# design.net
KiCad netlist of a schematic drawn in Altium Designer
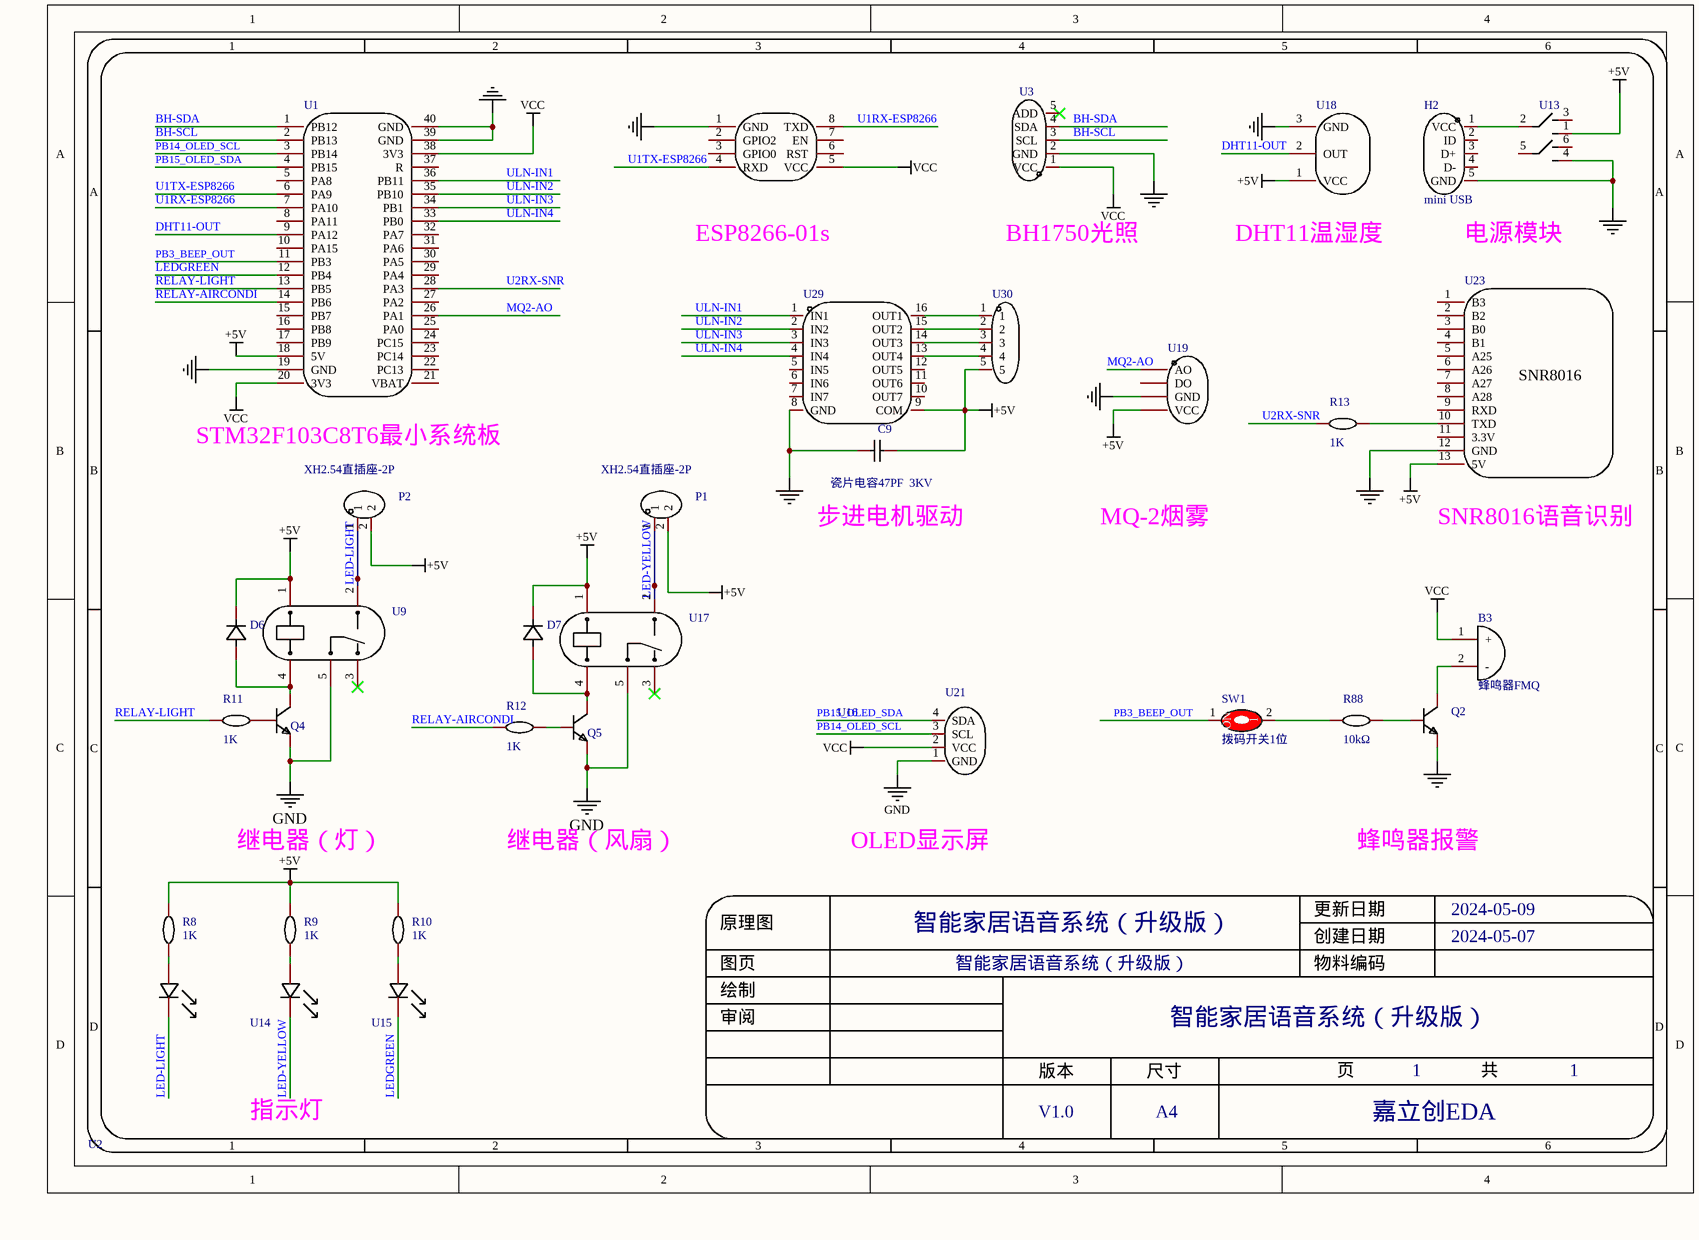
[diagram p0: 原理图.schdoc]

(export (version "E")
  (design (tool "Eeschema 10.0.6"))
  (components
    (comp (ref "B3")
      (value "蜂鸣器FMQ")
      (footprint "蜂鸣器")
      (fields (field (name "NAME") "蜂鸣器FMQ"))
      (libsource (lib "altium-import") (part "root_0_蜂鸣器FMQ_"))
    )
    (comp (ref "C9")
      (value "瓷片电容47PF  3KV")
      (footprint "CAP-TH_L5.0-W4.0-P5.00-D1.0")
      (fields (field (name "NAME") "瓷片电容47PF  3KV"))
      (libsource (lib "altium-import") (part "root_0_瓷片电容47PF  3KV_"))
    )
    (comp (ref "D6")
      (value "D_1N4007A")
      (footprint "DO_1N4007")
      (libsource (lib "altium-import") (part "root_1_D_1N4007A_"))
    )
    (comp (ref "D7")
      (value "D_1N4007A")
      (footprint "DO_1N4007")
      (libsource (lib "altium-import") (part "root_1_D_1N4007A_"))
    )
    (comp (ref "H2")
      (value "mini USB")
      (footprint "MINI-USB-POWER")
      (fields (field (name "NAME") "mini USB"))
      (libsource (lib "altium-import") (part "root_0_mini USB_"))
    )
    (comp (ref "P1")
      (value "XH2.54直插座-2P")
      (footprint "CONN-TH_XH2.54-2P")
      (fields (field (name "NAME") "XH2.54直插座-2P"))
      (libsource (lib "altium-import") (part "root_1_XH2.54直插座-2P_"))
    )
    (comp (ref "P2")
      (value "XH2.54直插座-2P")
      (footprint "CONN-TH_XH2.54-2P")
      (fields (field (name "NAME") "XH2.54直插座-2P"))
      (libsource (lib "altium-import") (part "root_1_XH2.54直插座-2P_"))
    )
    (comp (ref "Q2")
      (value "S8050_TO_NPN")
      (footprint "S8050_TO_92")
      (libsource (lib "altium-import") (part "root_0_S8050_TO_NPN_"))
    )
    (comp (ref "Q4")
      (value "S8050_TO_NPN")
      (footprint "S8050_TO_92")
      (libsource (lib "altium-import") (part "root_0_S8050_TO_NPN_"))
    )
    (comp (ref "Q5")
      (value "S8050_TO_NPN")
      (footprint "S8050_TO_92")
      (libsource (lib "altium-import") (part "root_0_S8050_TO_NPN_"))
    )
    (comp (ref "R8")
      (value "1K")
      (footprint "Res_1/4W")
      (fields (field (name "NAME") "1K"))
      (libsource (lib "altium-import") (part "root_1_Res_AXIAL-1/4W_"))
    )
    (comp (ref "R9")
      (value "1K")
      (footprint "Res_1/4W")
      (fields (field (name "NAME") "1K"))
      (libsource (lib "altium-import") (part "root_1_Res_AXIAL-1/4W_"))
    )
    (comp (ref "R10")
      (value "1K")
      (footprint "Res_1/4W")
      (fields (field (name "NAME") "1K"))
      (libsource (lib "altium-import") (part "root_1_Res_AXIAL-1/4W_"))
    )
    (comp (ref "R11")
      (value "1K")
      (footprint "Res_1/4W")
      (fields (field (name "NAME") "1K"))
      (libsource (lib "altium-import") (part "root_2_Res_AXIAL-1/4W_"))
    )
    (comp (ref "R12")
      (value "1K")
      (footprint "Res_1/4W")
      (fields (field (name "NAME") "1K"))
      (libsource (lib "altium-import") (part "root_2_Res_AXIAL-1/4W_"))
    )
    (comp (ref "R13")
      (value "1K")
      (footprint "Res_1/4W")
      (fields (field (name "NAME") "1K"))
      (libsource (lib "altium-import") (part "root_2_Res_AXIAL-1/4W_"))
    )
    (comp (ref "R88")
      (value "10kΩ")
      (footprint "Res_1/4W")
      (fields (field (name "NAME") "10kΩ"))
      (libsource (lib "altium-import") (part "root_0_Res_AXIAL-1/4W_"))
    )
    (comp (ref "SW1")
      (value "拨码开关1位")
      (footprint "SW-TH_DSWB01LHGET")
      (fields (field (name "NAME") "拨码开关1位"))
      (libsource (lib "altium-import") (part "root_1_拨码开关1位_"))
    )
    (comp (ref "U1")
      (value "STM32F103C8T6小蓝板")
      (footprint "STM32F103C8T6最小系统板(蓝)")
      (libsource (lib "altium-import") (part "root_0_STM32F103C8T6小蓝板_"))
    )
    (comp (ref "U2")
      (value "ESP8266-01S模块")
      (footprint "ESP8266-01S模块")
      (libsource (lib "altium-import") (part "root_0_ESP8266-01S模块_"))
    )
    (comp (ref "U3")
      (value "GY302光照传感器")
      (footprint "GY302光照传感器")
      (libsource (lib "altium-import") (part "root_0_GY302光照传感器_"))
    )
    (comp (ref "U9")
      (value "继电器5V")
      (footprint "继电器DC5V")
      (libsource (lib "altium-import") (part "root_3_继电器5V_"))
    )
    (comp (ref "U13")
      (value "按键开关7*7")
      (footprint "按键开关7*7")
      (libsource (lib "altium-import") (part "root_0_按键开关7*7_"))
    )
    (comp (ref "U14")
      (value "LED_5mm")
      (footprint "LED_5mm")
      (libsource (lib "altium-import") (part "root_3_LED_5mm_"))
    )
    (comp (ref "U15")
      (value "LED_5mm")
      (footprint "LED_5mm")
      (libsource (lib "altium-import") (part "root_3_LED_5mm_"))
    )
    (comp (ref "U16")
      (value "LED_5mm")
      (footprint "LED_5mm")
      (libsource (lib "altium-import") (part "root_3_LED_5mm_"))
    )
    (comp (ref "U17")
      (value "继电器5V")
      (footprint "继电器DC5V")
      (libsource (lib "altium-import") (part "root_3_继电器5V_"))
    )
    (comp (ref "U18")
      (value "DHT11温湿度传感器")
      (footprint "DHT11")
      (libsource (lib "altium-import") (part "root_0_DHT11温湿度传感器_"))
    )
    (comp (ref "U19")
      (value "MQ系列4针传感器")
      (footprint "MQ系列4针传感器")
      (libsource (lib "altium-import") (part "root_0_MQ系列4针传感器_"))
    )
    (comp (ref "U21")
      (value "OLED四针0.96寸")
      (footprint "OLED4针0.96寸")
      (libsource (lib "altium-import") (part "root_0_OLED四针0.96寸_"))
    )
    (comp (ref "U23")
      (value "SNR8016语音识别")
      (footprint "SNR8016")
      (libsource (lib "altium-import") (part "root_0_SNR8016语音识别_"))
    )
    (comp (ref "U29")
      (value "ULN2003A")
      (footprint "DIP-16_L20.0-W6.4-P2.54-LS7.6-BL")
      (fields (field (name "MANUFACTURER") "ST(意法半导体)"))
      (libsource (lib "altium-import") (part "root_0_ULN2003A_"))
    )
    (comp (ref "U30")
      (value "步进电机")
      (footprint "conn-th_5p-p2.54_xh2.54_5p_dip")
      (libsource (lib "altium-import") (part "root_0_步进电机_"))
    )
  )
  (nets
    (net (code "1") (name "+5V") (class "Default")
      (node (ref "C9") (pin "2") (pinfunction "2_2") (pintype "passive"))
      (node (ref "D6") (pin "1") (pinfunction "K_1") (pintype "passive"))
      (node (ref "D7") (pin "1") (pinfunction "K_1") (pintype "passive"))
      (node (ref "P1") (pin "2") (pinfunction "2_2") (pintype "passive"))
      (node (ref "P2") (pin "2") (pinfunction "2_2") (pintype "passive"))
      (node (ref "R10") (pin "2") (pinfunction "2_2") (pintype "passive"))
      (node (ref "R8") (pin "2") (pinfunction "2_2") (pintype "passive"))
      (node (ref "R9") (pin "2") (pinfunction "2_2") (pintype "passive"))
      (node (ref "U1") (pin "18") (pinfunction "5V_18") (pintype "passive"))
      (node (ref "U13") (pin "1") (pinfunction "1_1") (pintype "passive"))
      (node (ref "U17") (pin "1") (pinfunction "1_1") (pintype "passive"))
      (node (ref "U18") (pin "1") (pinfunction "VCC_1") (pintype "passive"))
      (node (ref "U19") (pin "4") (pinfunction "VCC_4") (pintype "passive"))
      (node (ref "U23") (pin "13") (pinfunction "5V_13") (pintype "passive"))
      (node (ref "U29") (pin "9") (pinfunction "COM_9") (pintype "passive"))
      (node (ref "U30") (pin "5") (pinfunction "5_5") (pintype "passive"))
      (node (ref "U9") (pin "1") (pinfunction "1_1") (pintype "passive"))
    )
    (net (code "2") (name "/BH-SCL") (class "Default")
      (node (ref "U1") (pin "2") (pinfunction "PB13_2") (pintype "passive"))
      (node (ref "U3") (pin "3") (pinfunction "SCL_3") (pintype "passive"))
    )
    (net (code "3") (name "/BH-SDA") (class "Default")
      (node (ref "U1") (pin "1") (pinfunction "PB12_1") (pintype "passive"))
      (node (ref "U3") (pin "4") (pinfunction "SDA_4") (pintype "passive"))
    )
    (net (code "4") (name "/DHT11-OUT") (class "Default")
      (node (ref "U1") (pin "9") (pinfunction "PA12_9") (pintype "passive"))
      (node (ref "U18") (pin "2") (pinfunction "OUT_2") (pintype "passive"))
    )
    (net (code "5") (name "/LED-LIGHT") (class "Default")
      (node (ref "P2") (pin "1") (pinfunction "1_1") (pintype "passive"))
      (node (ref "U14") (pin "1") (pinfunction "C_1") (pintype "passive"))
      (node (ref "U9") (pin "2") (pinfunction "2_2") (pintype "passive"))
    )
    (net (code "6") (name "/LED-YELLOW") (class "Default")
      (node (ref "P1") (pin "1") (pinfunction "1_1") (pintype "passive"))
      (node (ref "U15") (pin "1") (pinfunction "C_1") (pintype "passive"))
      (node (ref "U17") (pin "2") (pinfunction "2_2") (pintype "passive"))
    )
    (net (code "7") (name "/LEDGREEN") (class "Default")
      (node (ref "U1") (pin "12") (pinfunction "PB4_12") (pintype "passive"))
      (node (ref "U16") (pin "1") (pinfunction "C_1") (pintype "passive"))
    )
    (net (code "8") (name "/MQ2-AO") (class "Default")
      (node (ref "U1") (pin "26") (pinfunction "PA1_26") (pintype "passive"))
      (node (ref "U19") (pin "1") (pinfunction "AO_1") (pintype "passive"))
    )
    (net (code "9") (name "/PB3_BEEP_OUT") (class "Default")
      (node (ref "SW1") (pin "1") (pinfunction "1_1") (pintype "passive"))
      (node (ref "U1") (pin "11") (pinfunction "PB3_11") (pintype "passive"))
    )
    (net (code "10") (name "/PB14_OLED_SCL") (class "Default")
      (node (ref "U1") (pin "3") (pinfunction "PB14_3") (pintype "passive"))
      (node (ref "U21") (pin "3") (pinfunction "SCL_3") (pintype "passive"))
    )
    (net (code "11") (name "/PB15_OLED_SDA") (class "Default")
      (node (ref "U1") (pin "4") (pinfunction "PB15_4") (pintype "passive"))
      (node (ref "U21") (pin "4") (pinfunction "SDA_4") (pintype "passive"))
    )
    (net (code "12") (name "/RELAY-AIRCONDI") (class "Default")
      (node (ref "R12") (pin "2") (pinfunction "2_2") (pintype "passive"))
      (node (ref "U1") (pin "14") (pinfunction "PB6_14") (pintype "passive"))
    )
    (net (code "13") (name "/RELAY-LIGHT") (class "Default")
      (node (ref "R11") (pin "2") (pinfunction "2_2") (pintype "passive"))
      (node (ref "U1") (pin "13") (pinfunction "PB5_13") (pintype "passive"))
    )
    (net (code "14") (name "/U1RX-ESP8266") (class "Default")
      (node (ref "U1") (pin "7") (pinfunction "PA10_7") (pintype "passive"))
      (node (ref "U2") (pin "8") (pinfunction "TXD_8") (pintype "passive"))
    )
    (net (code "15") (name "/U1TX-ESP8266") (class "Default")
      (node (ref "U1") (pin "6") (pinfunction "PA9_6") (pintype "passive"))
      (node (ref "U2") (pin "4") (pinfunction "RXD_4") (pintype "passive"))
    )
    (net (code "16") (name "/U2RX-SNR") (class "Default")
      (node (ref "R13") (pin "2") (pinfunction "2_2") (pintype "passive"))
      (node (ref "U1") (pin "28") (pinfunction "PA3_28") (pintype "passive"))
    )
    (net (code "17") (name "/ULN-IN1") (class "Default")
      (node (ref "U1") (pin "36") (pinfunction "PB11_36") (pintype "passive"))
      (node (ref "U29") (pin "1") (pinfunction "IN1_1") (pintype "passive"))
    )
    (net (code "18") (name "/ULN-IN2") (class "Default")
      (node (ref "U1") (pin "35") (pinfunction "PB10_35") (pintype "passive"))
      (node (ref "U29") (pin "2") (pinfunction "IN2_2") (pintype "passive"))
    )
    (net (code "19") (name "/ULN-IN3") (class "Default")
      (node (ref "U1") (pin "34") (pinfunction "PB1_34") (pintype "passive"))
      (node (ref "U29") (pin "3") (pinfunction "IN3_3") (pintype "passive"))
    )
    (net (code "20") (name "/ULN-IN4") (class "Default")
      (node (ref "U1") (pin "33") (pinfunction "PB0_33") (pintype "passive"))
      (node (ref "U29") (pin "4") (pinfunction "IN4_4") (pintype "passive"))
    )
    (net (code "21") (name "<NO NET>") (class "Default")
      (node (ref "C9") (pin "1") (pinfunction "1_1") (pintype "passive"))
      (node (ref "H2") (pin "5") (pinfunction "GND_5") (pintype "passive"))
      (node (ref "Q2") (pin "1") (pinfunction "E_1") (pintype "passive"))
      (node (ref "U1") (pin "19") (pinfunction "GND_19") (pintype "passive"))
      (node (ref "U1") (pin "39") (pinfunction "GND_39") (pintype "passive"))
      (node (ref "U1") (pin "40") (pinfunction "GND_40") (pintype "passive"))
      (node (ref "U13") (pin "4") (pinfunction "4_4") (pintype "passive"))
      (node (ref "U18") (pin "3") (pinfunction "GND_3") (pintype "passive"))
      (node (ref "U19") (pin "3") (pinfunction "GND_3") (pintype "passive"))
      (node (ref "U2") (pin "1") (pinfunction "GND_1") (pintype "passive"))
      (node (ref "U23") (pin "12") (pinfunction "GND_12") (pintype "passive"))
      (node (ref "U29") (pin "8") (pinfunction "GND_8") (pintype "passive"))
      (node (ref "U3") (pin "2") (pinfunction "GND_2") (pintype "passive"))
    )
    (net (code "22") (name "GND") (class "Default")
      (node (ref "Q4") (pin "1") (pinfunction "E_1") (pintype "passive"))
      (node (ref "Q5") (pin "1") (pinfunction "E_1") (pintype "passive"))
      (node (ref "U17") (pin "5") (pinfunction "5_5") (pintype "passive"))
      (node (ref "U21") (pin "1") (pinfunction "GND_1") (pintype "passive"))
      (node (ref "U9") (pin "5") (pinfunction "5_5") (pintype "passive"))
    )
    (net (code "23") (name "Net-(B3--)") (class "Default")
      (node (ref "B3") (pin "2") (pinfunction "-_2") (pintype "passive"))
      (node (ref "Q2") (pin "3") (pinfunction "C_3") (pintype "passive"))
    )
    (net (code "24") (name "Net-(D6-A)") (class "Default")
      (node (ref "D6") (pin "2") (pinfunction "A_2") (pintype "passive"))
      (node (ref "Q4") (pin "3") (pinfunction "C_3") (pintype "passive"))
      (node (ref "U9") (pin "4") (pinfunction "4_4") (pintype "passive"))
    )
    (net (code "25") (name "Net-(D7-A)") (class "Default")
      (node (ref "D7") (pin "2") (pinfunction "A_2") (pintype "passive"))
      (node (ref "Q5") (pin "3") (pinfunction "C_3") (pintype "passive"))
      (node (ref "U17") (pin "4") (pinfunction "4_4") (pintype "passive"))
    )
    (net (code "26") (name "Net-(H2-VCC)") (class "Default")
      (node (ref "H2") (pin "1") (pinfunction "VCC_1") (pintype "passive"))
      (node (ref "U13") (pin "2") (pinfunction "2_2") (pintype "passive"))
    )
    (net (code "27") (name "Net-(Q2-B)") (class "Default")
      (node (ref "Q2") (pin "2") (pinfunction "B_2") (pintype "passive"))
      (node (ref "R88") (pin "2") (pinfunction "2_2") (pintype "passive"))
    )
    (net (code "28") (name "Net-(Q4-B)") (class "Default")
      (node (ref "Q4") (pin "2") (pinfunction "B_2") (pintype "passive"))
      (node (ref "R11") (pin "1") (pinfunction "1_1") (pintype "passive"))
    )
    (net (code "29") (name "Net-(Q5-B)") (class "Default")
      (node (ref "Q5") (pin "2") (pinfunction "B_2") (pintype "passive"))
      (node (ref "R12") (pin "1") (pinfunction "1_1") (pintype "passive"))
    )
    (net (code "30") (name "Net-(R88-Pad1)") (class "Default")
      (node (ref "R88") (pin "1") (pinfunction "1_1") (pintype "passive"))
      (node (ref "SW1") (pin "2") (pinfunction "2_2") (pintype "passive"))
    )
    (net (code "31") (name "Net-(U14-A)") (class "Default")
      (node (ref "R8") (pin "1") (pinfunction "1_1") (pintype "passive"))
      (node (ref "U14") (pin "2") (pinfunction "A_2") (pintype "passive"))
    )
    (net (code "32") (name "Net-(U15-A)") (class "Default")
      (node (ref "R9") (pin "1") (pinfunction "1_1") (pintype "passive"))
      (node (ref "U15") (pin "2") (pinfunction "A_2") (pintype "passive"))
    )
    (net (code "33") (name "Net-(U16-A)") (class "Default")
      (node (ref "R10") (pin "1") (pinfunction "1_1") (pintype "passive"))
      (node (ref "U16") (pin "2") (pinfunction "A_2") (pintype "passive"))
    )
    (net (code "34") (name "Net-(U23-TXD)") (class "Default")
      (node (ref "R13") (pin "1") (pinfunction "1_1") (pintype "passive"))
      (node (ref "U23") (pin "10") (pinfunction "TXD_10") (pintype "passive"))
    )
    (net (code "35") (name "Net-(U29-OUT1)") (class "Default")
      (node (ref "U29") (pin "16") (pinfunction "OUT1_16") (pintype "passive"))
      (node (ref "U30") (pin "1") (pinfunction "1_1") (pintype "passive"))
    )
    (net (code "36") (name "Net-(U29-OUT2)") (class "Default")
      (node (ref "U29") (pin "15") (pinfunction "OUT2_15") (pintype "passive"))
      (node (ref "U30") (pin "2") (pinfunction "2_2") (pintype "passive"))
    )
    (net (code "37") (name "Net-(U29-OUT3)") (class "Default")
      (node (ref "U29") (pin "14") (pinfunction "OUT3_14") (pintype "passive"))
      (node (ref "U30") (pin "3") (pinfunction "3_3") (pintype "passive"))
    )
    (net (code "38") (name "Net-(U29-OUT4)") (class "Default")
      (node (ref "U29") (pin "13") (pinfunction "OUT4_13") (pintype "passive"))
      (node (ref "U30") (pin "4") (pinfunction "4_4") (pintype "passive"))
    )
    (net (code "39") (name "VCC") (class "Default")
      (node (ref "B3") (pin "1") (pinfunction "+_1") (pintype "passive"))
      (node (ref "U1") (pin "20") (pinfunction "3V3_20") (pintype "passive"))
      (node (ref "U1") (pin "38") (pinfunction "3V3_38") (pintype "passive"))
      (node (ref "U2") (pin "5") (pinfunction "VCC_5") (pintype "passive"))
      (node (ref "U21") (pin "2") (pinfunction "VCC_2") (pintype "passive"))
      (node (ref "U3") (pin "1") (pinfunction "VCC_1") (pintype "passive"))
    )
    (net (code "40") (name "unconnected-(H2-D+-Pad3)") (class "Default")
      (node (ref "H2") (pin "3") (pinfunction "D+_3") (pintype "passive"))
    )
    (net (code "41") (name "unconnected-(H2-D--Pad4)") (class "Default")
      (node (ref "H2") (pin "4") (pinfunction "D-_4") (pintype "passive"))
    )
    (net (code "42") (name "unconnected-(H2-ID-Pad2)") (class "Default")
      (node (ref "H2") (pin "2") (pinfunction "ID_2") (pintype "passive"))
    )
    (net (code "43") (name "unconnected-(U1-PA0-Pad25)") (class "Default")
      (node (ref "U1") (pin "25") (pinfunction "PA0_25") (pintype "passive"))
    )
    (net (code "44") (name "unconnected-(U1-PA2-Pad27)") (class "Default")
      (node (ref "U1") (pin "27") (pinfunction "PA2_27") (pintype "passive"))
    )
    (net (code "45") (name "unconnected-(U1-PA4-Pad29)") (class "Default")
      (node (ref "U1") (pin "29") (pinfunction "PA4_29") (pintype "passive"))
    )
    (net (code "46") (name "unconnected-(U1-PA5-Pad30)") (class "Default")
      (node (ref "U1") (pin "30") (pinfunction "PA5_30") (pintype "passive"))
    )
    (net (code "47") (name "unconnected-(U1-PA6-Pad31)") (class "Default")
      (node (ref "U1") (pin "31") (pinfunction "PA6_31") (pintype "passive"))
    )
    (net (code "48") (name "unconnected-(U1-PA7-Pad32)") (class "Default")
      (node (ref "U1") (pin "32") (pinfunction "PA7_32") (pintype "passive"))
    )
    (net (code "49") (name "unconnected-(U1-PA8-Pad5)") (class "Default")
      (node (ref "U1") (pin "5") (pinfunction "PA8_5") (pintype "passive"))
    )
    (net (code "50") (name "unconnected-(U1-PA11-Pad8)") (class "Default")
      (node (ref "U1") (pin "8") (pinfunction "PA11_8") (pintype "passive"))
    )
    (net (code "51") (name "unconnected-(U1-PA15-Pad10)") (class "Default")
      (node (ref "U1") (pin "10") (pinfunction "PA15_10") (pintype "passive"))
    )
    (net (code "52") (name "unconnected-(U1-PB7-Pad15)") (class "Default")
      (node (ref "U1") (pin "15") (pinfunction "PB7_15") (pintype "passive"))
    )
    (net (code "53") (name "unconnected-(U1-PB8-Pad16)") (class "Default")
      (node (ref "U1") (pin "16") (pinfunction "PB8_16") (pintype "passive"))
    )
    (net (code "54") (name "unconnected-(U1-PB9-Pad17)") (class "Default")
      (node (ref "U1") (pin "17") (pinfunction "PB9_17") (pintype "passive"))
    )
    (net (code "55") (name "unconnected-(U1-PC13-Pad22)") (class "Default")
      (node (ref "U1") (pin "22") (pinfunction "PC13_22") (pintype "passive"))
    )
    (net (code "56") (name "unconnected-(U1-PC14-Pad23)") (class "Default")
      (node (ref "U1") (pin "23") (pinfunction "PC14_23") (pintype "passive"))
    )
    (net (code "57") (name "unconnected-(U1-PC15-Pad24)") (class "Default")
      (node (ref "U1") (pin "24") (pinfunction "PC15_24") (pintype "passive"))
    )
    (net (code "58") (name "unconnected-(U1-R-Pad37)") (class "Default")
      (node (ref "U1") (pin "37") (pinfunction "R_37") (pintype "passive"))
    )
    (net (code "59") (name "unconnected-(U1-VBAT-Pad21)") (class "Default")
      (node (ref "U1") (pin "21") (pinfunction "VBAT_21") (pintype "passive"))
    )
    (net (code "60") (name "unconnected-(U2-EN-Pad7)") (class "Default")
      (node (ref "U2") (pin "7") (pinfunction "EN_7") (pintype "passive"))
    )
    (net (code "61") (name "unconnected-(U2-GPIO0-Pad3)") (class "Default")
      (node (ref "U2") (pin "3") (pinfunction "GPIO0_3") (pintype "passive"))
    )
    (net (code "62") (name "unconnected-(U2-GPIO2-Pad2)") (class "Default")
      (node (ref "U2") (pin "2") (pinfunction "GPIO2_2") (pintype "passive"))
    )
    (net (code "63") (name "unconnected-(U2-RST-Pad6)") (class "Default")
      (node (ref "U2") (pin "6") (pinfunction "RST_6") (pintype "passive"))
    )
    (net (code "64") (name "unconnected-(U3-ADD-Pad5)") (class "Default")
      (node (ref "U3") (pin "5") (pinfunction "ADD_5") (pintype "passive+no_connect"))
    )
    (net (code "65") (name "unconnected-(U9-Pad3)") (class "Default")
      (node (ref "U9") (pin "3") (pinfunction "3_3") (pintype "passive+no_connect"))
    )
    (net (code "66") (name "unconnected-(U13-Pad3)") (class "Default")
      (node (ref "U13") (pin "3") (pinfunction "3_3") (pintype "passive"))
    )
    (net (code "67") (name "unconnected-(U13-Pad5)") (class "Default")
      (node (ref "U13") (pin "5") (pinfunction "5_5") (pintype "passive"))
    )
    (net (code "68") (name "unconnected-(U13-Pad6)") (class "Default")
      (node (ref "U13") (pin "6") (pinfunction "6_6") (pintype "passive"))
    )
    (net (code "69") (name "unconnected-(U17-Pad3)") (class "Default")
      (node (ref "U17") (pin "3") (pinfunction "3_3") (pintype "passive+no_connect"))
    )
    (net (code "70") (name "unconnected-(U19-DO-Pad2)") (class "Default")
      (node (ref "U19") (pin "2") (pinfunction "DO_2") (pintype "passive"))
    )
    (net (code "71") (name "unconnected-(U23-3.3V-Pad11)") (class "Default")
      (node (ref "U23") (pin "11") (pinfunction "3.3V_11") (pintype "passive"))
    )
    (net (code "72") (name "unconnected-(U23-A25-Pad5)") (class "Default")
      (node (ref "U23") (pin "5") (pinfunction "A25_5") (pintype "passive"))
    )
    (net (code "73") (name "unconnected-(U23-A26-Pad6)") (class "Default")
      (node (ref "U23") (pin "6") (pinfunction "A26_6") (pintype "passive"))
    )
    (net (code "74") (name "unconnected-(U23-A27-Pad7)") (class "Default")
      (node (ref "U23") (pin "7") (pinfunction "A27_7") (pintype "passive"))
    )
    (net (code "75") (name "unconnected-(U23-A28-Pad8)") (class "Default")
      (node (ref "U23") (pin "8") (pinfunction "A28_8") (pintype "passive"))
    )
    (net (code "76") (name "unconnected-(U23-B0-Pad3)") (class "Default")
      (node (ref "U23") (pin "3") (pinfunction "B0_3") (pintype "passive"))
    )
    (net (code "77") (name "unconnected-(U23-B1-Pad4)") (class "Default")
      (node (ref "U23") (pin "4") (pinfunction "B1_4") (pintype "passive"))
    )
    (net (code "78") (name "unconnected-(U23-B2-Pad2)") (class "Default")
      (node (ref "U23") (pin "2") (pinfunction "B2_2") (pintype "passive"))
    )
    (net (code "79") (name "unconnected-(U23-B3-Pad1)") (class "Default")
      (node (ref "U23") (pin "1") (pinfunction "B3_1") (pintype "passive"))
    )
    (net (code "80") (name "unconnected-(U23-RXD-Pad9)") (class "Default")
      (node (ref "U23") (pin "9") (pinfunction "RXD_9") (pintype "passive"))
    )
    (net (code "81") (name "unconnected-(U29-IN5-Pad5)") (class "Default")
      (node (ref "U29") (pin "5") (pinfunction "IN5_5") (pintype "passive"))
    )
    (net (code "82") (name "unconnected-(U29-IN6-Pad6)") (class "Default")
      (node (ref "U29") (pin "6") (pinfunction "IN6_6") (pintype "passive"))
    )
    (net (code "83") (name "unconnected-(U29-IN7-Pad7)") (class "Default")
      (node (ref "U29") (pin "7") (pinfunction "IN7_7") (pintype "passive"))
    )
    (net (code "84") (name "unconnected-(U29-OUT5-Pad12)") (class "Default")
      (node (ref "U29") (pin "12") (pinfunction "OUT5_12") (pintype "passive"))
    )
    (net (code "85") (name "unconnected-(U29-OUT6-Pad11)") (class "Default")
      (node (ref "U29") (pin "11") (pinfunction "OUT6_11") (pintype "passive"))
    )
    (net (code "86") (name "unconnected-(U29-OUT7-Pad10)") (class "Default")
      (node (ref "U29") (pin "10") (pinfunction "OUT7_10") (pintype "passive"))
    )
  )
)
